# Sitara_Power.net
KiCad netlist of a schematic drawn in Altium Designer
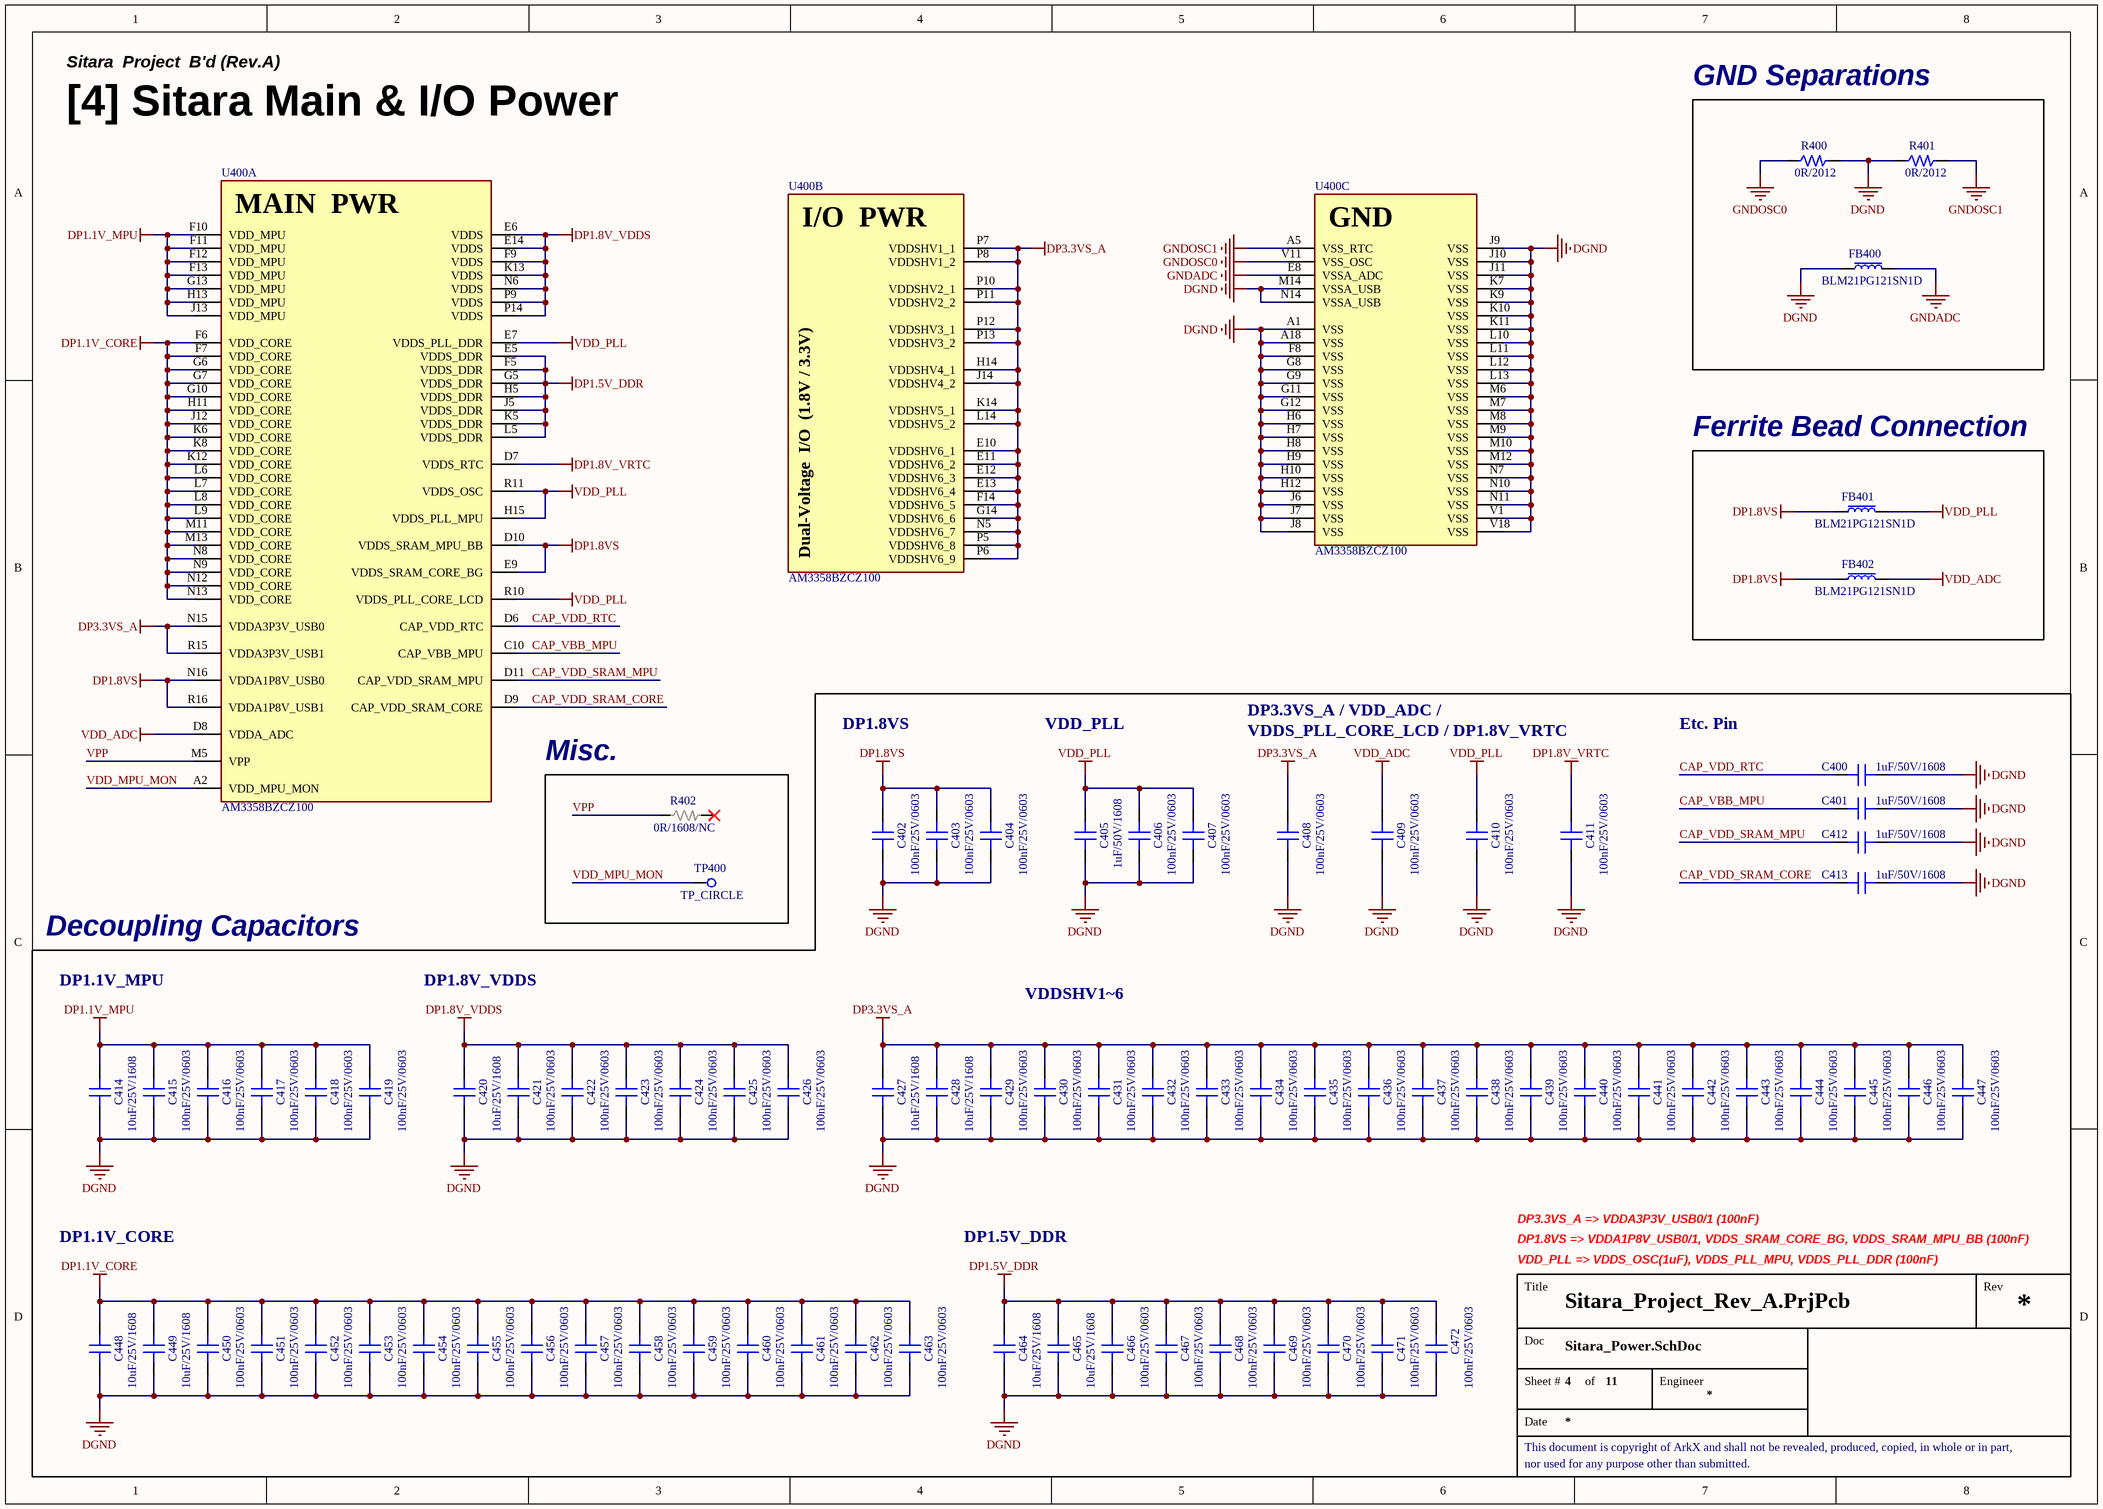
[diagram p0: Sitara_Power.SchDoc]

(export (version "E")
  (design (tool "Eeschema 10.0.6"))
  (components
    (comp (ref "C400")
      (value "1uF/50V/1608")
      (footprint "CAP 1608 (0603_INCH)")
      (description "Ceramic CAP_1uF/50V/1608")
      (fields (field (name "LCSC PART #") "C15849"))
      (libsource (lib "Arkx") (part "CAP_1uF/50V/1608"))
    )
    (comp (ref "C401")
      (value "1uF/50V/1608")
      (footprint "CAP 1608 (0603_INCH)")
      (description "Ceramic CAP_1uF/50V/1608")
      (fields (field (name "LCSC PART #") "C15849"))
      (libsource (lib "Arkx") (part "CAP_1uF/50V/1608"))
    )
    (comp (ref "C402")
      (value "100nF/25V/0603")
      (footprint "CAP 0603 (0201_INCH)")
      (description "Ceramic CAP_100nF/25V/0603")
      (fields (field (name "LCSC PART #") "C181047"))
      (libsource (lib "Arkx") (part "CAP_100nF/25V/0603"))
    )
    (comp (ref "C403")
      (value "100nF/25V/0603")
      (footprint "CAP 0603 (0201_INCH)")
      (description "Ceramic CAP_100nF/25V/0603")
      (fields (field (name "LCSC PART #") "C181047"))
      (libsource (lib "Arkx") (part "CAP_100nF/25V/0603"))
    )
    (comp (ref "C404")
      (value "100nF/25V/0603")
      (footprint "CAP 0603 (0201_INCH)")
      (description "Ceramic CAP_100nF/25V/0603")
      (fields (field (name "LCSC PART #") "C181047"))
      (libsource (lib "Arkx") (part "CAP_100nF/25V/0603"))
    )
    (comp (ref "C405")
      (value "1uF/50V/1608")
      (footprint "CAP 1608 (0603_INCH)")
      (description "Ceramic CAP_1uF/50V/1608")
      (fields (field (name "LCSC PART #") "C15849"))
      (libsource (lib "Arkx") (part "CAP_1uF/50V/1608"))
    )
    (comp (ref "C406")
      (value "100nF/25V/0603")
      (footprint "CAP 0603 (0201_INCH)")
      (description "Ceramic CAP_100nF/25V/0603")
      (fields (field (name "LCSC PART #") "C181047"))
      (libsource (lib "Arkx") (part "CAP_100nF/25V/0603"))
    )
    (comp (ref "C407")
      (value "100nF/25V/0603")
      (footprint "CAP 0603 (0201_INCH)")
      (description "Ceramic CAP_100nF/25V/0603")
      (fields (field (name "LCSC PART #") "C181047"))
      (libsource (lib "Arkx") (part "CAP_100nF/25V/0603"))
    )
    (comp (ref "C408")
      (value "100nF/25V/0603")
      (footprint "CAP 0603 (0201_INCH)")
      (description "Ceramic CAP_100nF/25V/0603")
      (fields (field (name "LCSC PART #") "C181047"))
      (libsource (lib "Arkx") (part "CAP_100nF/25V/0603"))
    )
    (comp (ref "C409")
      (value "100nF/25V/0603")
      (footprint "CAP 0603 (0201_INCH)")
      (description "Ceramic CAP_100nF/25V/0603")
      (fields (field (name "LCSC PART #") "C181047"))
      (libsource (lib "Arkx") (part "CAP_100nF/25V/0603"))
    )
    (comp (ref "C410")
      (value "100nF/25V/0603")
      (footprint "CAP 0603 (0201_INCH)")
      (description "Ceramic CAP_100nF/25V/0603")
      (fields (field (name "LCSC PART #") "C181047"))
      (libsource (lib "Arkx") (part "CAP_100nF/25V/0603"))
    )
    (comp (ref "C411")
      (value "100nF/25V/0603")
      (footprint "CAP 0603 (0201_INCH)")
      (description "Ceramic CAP_100nF/25V/0603")
      (fields (field (name "LCSC PART #") "C181047"))
      (libsource (lib "Arkx") (part "CAP_100nF/25V/0603"))
    )
    (comp (ref "C412")
      (value "1uF/50V/1608")
      (footprint "CAP 1608 (0603_INCH)")
      (description "Ceramic CAP_1uF/50V/1608")
      (fields (field (name "LCSC PART #") "C15849"))
      (libsource (lib "Arkx") (part "CAP_1uF/50V/1608"))
    )
    (comp (ref "C413")
      (value "1uF/50V/1608")
      (footprint "CAP 1608 (0603_INCH)")
      (description "Ceramic CAP_1uF/50V/1608")
      (fields (field (name "LCSC PART #") "C15849"))
      (libsource (lib "Arkx") (part "CAP_1uF/50V/1608"))
    )
    (comp (ref "C414")
      (value "10uF/25V/1608")
      (footprint "CAP 1608 (0603_INCH)")
      (description "Ceramic CAP_10uF/25V/1608")
      (fields (field (name "LCSC PART #") "C96446"))
      (libsource (lib "Arkx") (part "CAP_10uF/25V/1608"))
    )
    (comp (ref "C415")
      (value "100nF/25V/0603")
      (footprint "CAP 0603 (0201_INCH)")
      (description "Ceramic CAP_100nF/25V/0603")
      (fields (field (name "LCSC PART #") "C181047"))
      (libsource (lib "Arkx") (part "CAP_100nF/25V/0603"))
    )
    (comp (ref "C416")
      (value "100nF/25V/0603")
      (footprint "CAP 0603 (0201_INCH)")
      (description "Ceramic CAP_100nF/25V/0603")
      (fields (field (name "LCSC PART #") "C181047"))
      (libsource (lib "Arkx") (part "CAP_100nF/25V/0603"))
    )
    (comp (ref "C417")
      (value "100nF/25V/0603")
      (footprint "CAP 0603 (0201_INCH)")
      (description "Ceramic CAP_100nF/25V/0603")
      (fields (field (name "LCSC PART #") "C181047"))
      (libsource (lib "Arkx") (part "CAP_100nF/25V/0603"))
    )
    (comp (ref "C418")
      (value "100nF/25V/0603")
      (footprint "CAP 0603 (0201_INCH)")
      (description "Ceramic CAP_100nF/25V/0603")
      (fields (field (name "LCSC PART #") "C181047"))
      (libsource (lib "Arkx") (part "CAP_100nF/25V/0603"))
    )
    (comp (ref "C419")
      (value "100nF/25V/0603")
      (footprint "CAP 0603 (0201_INCH)")
      (description "Ceramic CAP_100nF/25V/0603")
      (fields (field (name "LCSC PART #") "C181047"))
      (libsource (lib "Arkx") (part "CAP_100nF/25V/0603"))
    )
    (comp (ref "C420")
      (value "10uF/25V/1608")
      (footprint "CAP 1608 (0603_INCH)")
      (description "Ceramic CAP_10uF/25V/1608")
      (fields (field (name "LCSC PART #") "C96446"))
      (libsource (lib "Arkx") (part "CAP_10uF/25V/1608"))
    )
    (comp (ref "C421")
      (value "100nF/25V/0603")
      (footprint "CAP 0603 (0201_INCH)")
      (description "Ceramic CAP_100nF/25V/0603")
      (fields (field (name "LCSC PART #") "C181047"))
      (libsource (lib "Arkx") (part "CAP_100nF/25V/0603"))
    )
    (comp (ref "C422")
      (value "100nF/25V/0603")
      (footprint "CAP 0603 (0201_INCH)")
      (description "Ceramic CAP_100nF/25V/0603")
      (fields (field (name "LCSC PART #") "C181047"))
      (libsource (lib "Arkx") (part "CAP_100nF/25V/0603"))
    )
    (comp (ref "C423")
      (value "100nF/25V/0603")
      (footprint "CAP 0603 (0201_INCH)")
      (description "Ceramic CAP_100nF/25V/0603")
      (fields (field (name "LCSC PART #") "C181047"))
      (libsource (lib "Arkx") (part "CAP_100nF/25V/0603"))
    )
    (comp (ref "C424")
      (value "100nF/25V/0603")
      (footprint "CAP 0603 (0201_INCH)")
      (description "Ceramic CAP_100nF/25V/0603")
      (fields (field (name "LCSC PART #") "C181047"))
      (libsource (lib "Arkx") (part "CAP_100nF/25V/0603"))
    )
    (comp (ref "C425")
      (value "100nF/25V/0603")
      (footprint "CAP 0603 (0201_INCH)")
      (description "Ceramic CAP_100nF/25V/0603")
      (fields (field (name "LCSC PART #") "C181047"))
      (libsource (lib "Arkx") (part "CAP_100nF/25V/0603"))
    )
    (comp (ref "C426")
      (value "100nF/25V/0603")
      (footprint "CAP 0603 (0201_INCH)")
      (description "Ceramic CAP_100nF/25V/0603")
      (fields (field (name "LCSC PART #") "C181047"))
      (libsource (lib "Arkx") (part "CAP_100nF/25V/0603"))
    )
    (comp (ref "C427")
      (value "10uF/25V/1608")
      (footprint "CAP 1608 (0603_INCH)")
      (description "Ceramic CAP_10uF/25V/1608")
      (fields (field (name "LCSC PART #") "C96446"))
      (libsource (lib "Arkx") (part "CAP_10uF/25V/1608"))
    )
    (comp (ref "C428")
      (value "10uF/25V/1608")
      (footprint "CAP 1608 (0603_INCH)")
      (description "Ceramic CAP_10uF/25V/1608")
      (fields (field (name "LCSC PART #") "C96446"))
      (libsource (lib "Arkx") (part "CAP_10uF/25V/1608"))
    )
    (comp (ref "C429")
      (value "100nF/25V/0603")
      (footprint "CAP 0603 (0201_INCH)")
      (description "Ceramic CAP_100nF/25V/0603")
      (fields (field (name "LCSC PART #") "C181047"))
      (libsource (lib "Arkx") (part "CAP_100nF/25V/0603"))
    )
    (comp (ref "C430")
      (value "100nF/25V/0603")
      (footprint "CAP 0603 (0201_INCH)")
      (description "Ceramic CAP_100nF/25V/0603")
      (fields (field (name "LCSC PART #") "C181047"))
      (libsource (lib "Arkx") (part "CAP_100nF/25V/0603"))
    )
    (comp (ref "C431")
      (value "100nF/25V/0603")
      (footprint "CAP 0603 (0201_INCH)")
      (description "Ceramic CAP_100nF/25V/0603")
      (fields (field (name "LCSC PART #") "C181047"))
      (libsource (lib "Arkx") (part "CAP_100nF/25V/0603"))
    )
    (comp (ref "C432")
      (value "100nF/25V/0603")
      (footprint "CAP 0603 (0201_INCH)")
      (description "Ceramic CAP_100nF/25V/0603")
      (fields (field (name "LCSC PART #") "C181047"))
      (libsource (lib "Arkx") (part "CAP_100nF/25V/0603"))
    )
    (comp (ref "C433")
      (value "100nF/25V/0603")
      (footprint "CAP 0603 (0201_INCH)")
      (description "Ceramic CAP_100nF/25V/0603")
      (fields (field (name "LCSC PART #") "C181047"))
      (libsource (lib "Arkx") (part "CAP_100nF/25V/0603"))
    )
    (comp (ref "C434")
      (value "100nF/25V/0603")
      (footprint "CAP 0603 (0201_INCH)")
      (description "Ceramic CAP_100nF/25V/0603")
      (fields (field (name "LCSC PART #") "C181047"))
      (libsource (lib "Arkx") (part "CAP_100nF/25V/0603"))
    )
    (comp (ref "C435")
      (value "100nF/25V/0603")
      (footprint "CAP 0603 (0201_INCH)")
      (description "Ceramic CAP_100nF/25V/0603")
      (fields (field (name "LCSC PART #") "C181047"))
      (libsource (lib "Arkx") (part "CAP_100nF/25V/0603"))
    )
    (comp (ref "C436")
      (value "100nF/25V/0603")
      (footprint "CAP 0603 (0201_INCH)")
      (description "Ceramic CAP_100nF/25V/0603")
      (fields (field (name "LCSC PART #") "C181047"))
      (libsource (lib "Arkx") (part "CAP_100nF/25V/0603"))
    )
    (comp (ref "C437")
      (value "100nF/25V/0603")
      (footprint "CAP 0603 (0201_INCH)")
      (description "Ceramic CAP_100nF/25V/0603")
      (fields (field (name "LCSC PART #") "C181047"))
      (libsource (lib "Arkx") (part "CAP_100nF/25V/0603"))
    )
    (comp (ref "C438")
      (value "100nF/25V/0603")
      (footprint "CAP 0603 (0201_INCH)")
      (description "Ceramic CAP_100nF/25V/0603")
      (fields (field (name "LCSC PART #") "C181047"))
      (libsource (lib "Arkx") (part "CAP_100nF/25V/0603"))
    )
    (comp (ref "C439")
      (value "100nF/25V/0603")
      (footprint "CAP 0603 (0201_INCH)")
      (description "Ceramic CAP_100nF/25V/0603")
      (fields (field (name "LCSC PART #") "C181047"))
      (libsource (lib "Arkx") (part "CAP_100nF/25V/0603"))
    )
    (comp (ref "C440")
      (value "100nF/25V/0603")
      (footprint "CAP 0603 (0201_INCH)")
      (description "Ceramic CAP_100nF/25V/0603")
      (fields (field (name "LCSC PART #") "C181047"))
      (libsource (lib "Arkx") (part "CAP_100nF/25V/0603"))
    )
    (comp (ref "C441")
      (value "100nF/25V/0603")
      (footprint "CAP 0603 (0201_INCH)")
      (description "Ceramic CAP_100nF/25V/0603")
      (fields (field (name "LCSC PART #") "C181047"))
      (libsource (lib "Arkx") (part "CAP_100nF/25V/0603"))
    )
    (comp (ref "C442")
      (value "100nF/25V/0603")
      (footprint "CAP 0603 (0201_INCH)")
      (description "Ceramic CAP_100nF/25V/0603")
      (fields (field (name "LCSC PART #") "C181047"))
      (libsource (lib "Arkx") (part "CAP_100nF/25V/0603"))
    )
    (comp (ref "C443")
      (value "100nF/25V/0603")
      (footprint "CAP 0603 (0201_INCH)")
      (description "Ceramic CAP_100nF/25V/0603")
      (fields (field (name "LCSC PART #") "C181047"))
      (libsource (lib "Arkx") (part "CAP_100nF/25V/0603"))
    )
    (comp (ref "C444")
      (value "100nF/25V/0603")
      (footprint "CAP 0603 (0201_INCH)")
      (description "Ceramic CAP_100nF/25V/0603")
      (fields (field (name "LCSC PART #") "C181047"))
      (libsource (lib "Arkx") (part "CAP_100nF/25V/0603"))
    )
    (comp (ref "C445")
      (value "100nF/25V/0603")
      (footprint "CAP 0603 (0201_INCH)")
      (description "Ceramic CAP_100nF/25V/0603")
      (fields (field (name "LCSC PART #") "C181047"))
      (libsource (lib "Arkx") (part "CAP_100nF/25V/0603"))
    )
    (comp (ref "C446")
      (value "100nF/25V/0603")
      (footprint "CAP 0603 (0201_INCH)")
      (description "Ceramic CAP_100nF/25V/0603")
      (fields (field (name "LCSC PART #") "C181047"))
      (libsource (lib "Arkx") (part "CAP_100nF/25V/0603"))
    )
    (comp (ref "C447")
      (value "100nF/25V/0603")
      (footprint "CAP 0603 (0201_INCH)")
      (description "Ceramic CAP_100nF/25V/0603")
      (fields (field (name "LCSC PART #") "C181047"))
      (libsource (lib "Arkx") (part "CAP_100nF/25V/0603"))
    )
    (comp (ref "C448")
      (value "10uF/25V/1608")
      (footprint "CAP 1608 (0603_INCH)")
      (description "Ceramic CAP_10uF/25V/1608")
      (fields (field (name "LCSC PART #") "C96446"))
      (libsource (lib "Arkx") (part "CAP_10uF/25V/1608"))
    )
    (comp (ref "C449")
      (value "10uF/25V/1608")
      (footprint "CAP 1608 (0603_INCH)")
      (description "Ceramic CAP_10uF/25V/1608")
      (fields (field (name "LCSC PART #") "C96446"))
      (libsource (lib "Arkx") (part "CAP_10uF/25V/1608"))
    )
    (comp (ref "C450")
      (value "100nF/25V/0603")
      (footprint "CAP 0603 (0201_INCH)")
      (description "Ceramic CAP_100nF/25V/0603")
      (fields (field (name "LCSC PART #") "C181047"))
      (libsource (lib "Arkx") (part "CAP_100nF/25V/0603"))
    )
    (comp (ref "C451")
      (value "100nF/25V/0603")
      (footprint "CAP 0603 (0201_INCH)")
      (description "Ceramic CAP_100nF/25V/0603")
      (fields (field (name "LCSC PART #") "C181047"))
      (libsource (lib "Arkx") (part "CAP_100nF/25V/0603"))
    )
    (comp (ref "C452")
      (value "100nF/25V/0603")
      (footprint "CAP 0603 (0201_INCH)")
      (description "Ceramic CAP_100nF/25V/0603")
      (fields (field (name "LCSC PART #") "C181047"))
      (libsource (lib "Arkx") (part "CAP_100nF/25V/0603"))
    )
    (comp (ref "C453")
      (value "100nF/25V/0603")
      (footprint "CAP 0603 (0201_INCH)")
      (description "Ceramic CAP_100nF/25V/0603")
      (fields (field (name "LCSC PART #") "C181047"))
      (libsource (lib "Arkx") (part "CAP_100nF/25V/0603"))
    )
    (comp (ref "C454")
      (value "100nF/25V/0603")
      (footprint "CAP 0603 (0201_INCH)")
      (description "Ceramic CAP_100nF/25V/0603")
      (fields (field (name "LCSC PART #") "C181047"))
      (libsource (lib "Arkx") (part "CAP_100nF/25V/0603"))
    )
    (comp (ref "C455")
      (value "100nF/25V/0603")
      (footprint "CAP 0603 (0201_INCH)")
      (description "Ceramic CAP_100nF/25V/0603")
      (fields (field (name "LCSC PART #") "C181047"))
      (libsource (lib "Arkx") (part "CAP_100nF/25V/0603"))
    )
    (comp (ref "C456")
      (value "100nF/25V/0603")
      (footprint "CAP 0603 (0201_INCH)")
      (description "Ceramic CAP_100nF/25V/0603")
      (fields (field (name "LCSC PART #") "C181047"))
      (libsource (lib "Arkx") (part "CAP_100nF/25V/0603"))
    )
    (comp (ref "C457")
      (value "100nF/25V/0603")
      (footprint "CAP 0603 (0201_INCH)")
      (description "Ceramic CAP_100nF/25V/0603")
      (fields (field (name "LCSC PART #") "C181047"))
      (libsource (lib "Arkx") (part "CAP_100nF/25V/0603"))
    )
    (comp (ref "C458")
      (value "100nF/25V/0603")
      (footprint "CAP 0603 (0201_INCH)")
      (description "Ceramic CAP_100nF/25V/0603")
      (fields (field (name "LCSC PART #") "C181047"))
      (libsource (lib "Arkx") (part "CAP_100nF/25V/0603"))
    )
    (comp (ref "C459")
      (value "100nF/25V/0603")
      (footprint "CAP 0603 (0201_INCH)")
      (description "Ceramic CAP_100nF/25V/0603")
      (fields (field (name "LCSC PART #") "C181047"))
      (libsource (lib "Arkx") (part "CAP_100nF/25V/0603"))
    )
    (comp (ref "C460")
      (value "100nF/25V/0603")
      (footprint "CAP 0603 (0201_INCH)")
      (description "Ceramic CAP_100nF/25V/0603")
      (fields (field (name "LCSC PART #") "C181047"))
      (libsource (lib "Arkx") (part "CAP_100nF/25V/0603"))
    )
    (comp (ref "C461")
      (value "100nF/25V/0603")
      (footprint "CAP 0603 (0201_INCH)")
      (description "Ceramic CAP_100nF/25V/0603")
      (fields (field (name "LCSC PART #") "C181047"))
      (libsource (lib "Arkx") (part "CAP_100nF/25V/0603"))
    )
    (comp (ref "C462")
      (value "100nF/25V/0603")
      (footprint "CAP 0603 (0201_INCH)")
      (description "Ceramic CAP_100nF/25V/0603")
      (fields (field (name "LCSC PART #") "C181047"))
      (libsource (lib "Arkx") (part "CAP_100nF/25V/0603"))
    )
    (comp (ref "C463")
      (value "100nF/25V/0603")
      (footprint "CAP 0603 (0201_INCH)")
      (description "Ceramic CAP_100nF/25V/0603")
      (fields (field (name "LCSC PART #") "C181047"))
      (libsource (lib "Arkx") (part "CAP_100nF/25V/0603"))
    )
    (comp (ref "C464")
      (value "10uF/25V/1608")
      (footprint "CAP 1608 (0603_INCH)")
      (description "Ceramic CAP_10uF/25V/1608")
      (fields (field (name "LCSC PART #") "C96446"))
      (libsource (lib "Arkx") (part "CAP_10uF/25V/1608"))
    )
    (comp (ref "C465")
      (value "10uF/25V/1608")
      (footprint "CAP 1608 (0603_INCH)")
      (description "Ceramic CAP_10uF/25V/1608")
      (fields (field (name "LCSC PART #") "C96446"))
      (libsource (lib "Arkx") (part "CAP_10uF/25V/1608"))
    )
    (comp (ref "C466")
      (value "100nF/25V/0603")
      (footprint "CAP 0603 (0201_INCH)")
      (description "Ceramic CAP_100nF/25V/0603")
      (fields (field (name "LCSC PART #") "C181047"))
      (libsource (lib "Arkx") (part "CAP_100nF/25V/0603"))
    )
    (comp (ref "C467")
      (value "100nF/25V/0603")
      (footprint "CAP 0603 (0201_INCH)")
      (description "Ceramic CAP_100nF/25V/0603")
      (fields (field (name "LCSC PART #") "C181047"))
      (libsource (lib "Arkx") (part "CAP_100nF/25V/0603"))
    )
    (comp (ref "C468")
      (value "100nF/25V/0603")
      (footprint "CAP 0603 (0201_INCH)")
      (description "Ceramic CAP_100nF/25V/0603")
      (fields (field (name "LCSC PART #") "C181047"))
      (libsource (lib "Arkx") (part "CAP_100nF/25V/0603"))
    )
    (comp (ref "C469")
      (value "100nF/25V/0603")
      (footprint "CAP 0603 (0201_INCH)")
      (description "Ceramic CAP_100nF/25V/0603")
      (fields (field (name "LCSC PART #") "C181047"))
      (libsource (lib "Arkx") (part "CAP_100nF/25V/0603"))
    )
    (comp (ref "C470")
      (value "100nF/25V/0603")
      (footprint "CAP 0603 (0201_INCH)")
      (description "Ceramic CAP_100nF/25V/0603")
      (fields (field (name "LCSC PART #") "C181047"))
      (libsource (lib "Arkx") (part "CAP_100nF/25V/0603"))
    )
    (comp (ref "C471")
      (value "100nF/25V/0603")
      (footprint "CAP 0603 (0201_INCH)")
      (description "Ceramic CAP_100nF/25V/0603")
      (fields (field (name "LCSC PART #") "C181047"))
      (libsource (lib "Arkx") (part "CAP_100nF/25V/0603"))
    )
    (comp (ref "C472")
      (value "100nF/25V/0603")
      (footprint "CAP 0603 (0201_INCH)")
      (description "Ceramic CAP_100nF/25V/0603")
      (fields (field (name "LCSC PART #") "C181047"))
      (libsource (lib "Arkx") (part "CAP_100nF/25V/0603"))
    )
    (comp (ref "FB400")
      (value "BLM21PG121SN1D")
      (footprint "FB 2012 (0805_inch)")
      (description "3A 1 30mΩ 120Ω@100MHz ±25% 0805  Ferrite Beads ROHS")
      (fields (field (name "LCSC PART #") "C79382"))
      (libsource (lib "Arkx") (part "FB_BLM21PG121SN1D"))
    )
    (comp (ref "FB401")
      (value "BLM21PG121SN1D")
      (footprint "FB 2012 (0805_inch)")
      (description "3A 1 30mΩ 120Ω@100MHz ±25% 0805  Ferrite Beads ROHS")
      (fields (field (name "LCSC PART #") "C79382"))
      (libsource (lib "Arkx") (part "FB_BLM21PG121SN1D"))
    )
    (comp (ref "FB402")
      (value "BLM21PG121SN1D")
      (footprint "FB 2012 (0805_inch)")
      (description "3A 1 30mΩ 120Ω@100MHz ±25% 0805  Ferrite Beads ROHS")
      (fields (field (name "LCSC PART #") "C79382"))
      (libsource (lib "Arkx") (part "FB_BLM21PG121SN1D"))
    )
    (comp (ref "R400")
      (value "0R/2012")
      (footprint "RES 2012 (0805_inch)")
      (description "RES_0R/2012/0.125W")
      (fields (field (name "LCSC PART #") "C17477"))
      (libsource (lib "Arkx") (part "RES_0R/2012/0.125W"))
    )
    (comp (ref "R401")
      (value "0R/2012")
      (footprint "RES 2012 (0805_inch)")
      (description "RES_0R/2012/0.125W")
      (fields (field (name "LCSC PART #") "C17477"))
      (libsource (lib "Arkx") (part "RES_0R/2012/0.125W"))
    )
    (comp (ref "R402")
      (value "0R/1608/NC")
      (footprint "RES 1608 (0603_inch)/NC")
      (description "0R/1608/0.1W/NC")
      (libsource (lib "Arkx") (part "RES_NC_0R/1608/0.1W"))
    )
    (comp (ref "TP400")
      (value "TP_CIRCLE")
      (footprint "TP Circle")
      (libsource (lib "Arkx") (part "TP_CIRCLE"))
    )
    (comp (ref "U400")
      (value "AM3358BZCZ100")
      (footprint "IC_SOC_AM3358BZCZ100")
      (description "ARM® Cortex®-A8 Microprocessor IC Sitara™ 1 Core, 32-Bit 1.0GHz 324-NFBGA (15x15)")
      (fields (field (name "LCSC PART #") "C73932"))
      (libsource (lib "Arkx") (part "IC_SOC_AM3358BZCZ100"))
    )
  )
  (nets
    (net (code "1") (name "/CAP_VBB_MPU") (class "Default")
      (node (ref "C401") (pin "1") (pinfunction "1_1") (pintype "passive"))
      (node (ref "U400") (pin "C10") (pinfunction "CAP_VBB_MPU_C10") (pintype "power_in"))
    )
    (net (code "2") (name "/CAP_VDD_RTC") (class "Default")
      (node (ref "C400") (pin "1") (pinfunction "1_1") (pintype "passive"))
      (node (ref "U400") (pin "D6") (pinfunction "CAP_VDD_RTC_D6") (pintype "power_in"))
    )
    (net (code "3") (name "/CAP_VDD_SRAM_CORE") (class "Default")
      (node (ref "C413") (pin "1") (pinfunction "1_1") (pintype "passive"))
      (node (ref "U400") (pin "D9") (pinfunction "CAP_VDD_SRAM_CORE_D9") (pintype "power_in"))
    )
    (net (code "4") (name "/CAP_VDD_SRAM_MPU") (class "Default")
      (node (ref "C412") (pin "1") (pinfunction "1_1") (pintype "passive"))
      (node (ref "U400") (pin "D11") (pinfunction "CAP_VDD_SRAM_MPU_D11") (pintype "power_in"))
    )
    (net (code "5") (name "/VDD_MPU_MON") (class "Default")
      (node (ref "TP400") (pin "1") (pinfunction "TP_1") (pintype "passive"))
      (node (ref "U400") (pin "A2") (pinfunction "VDD_MPU_MON_A2") (pintype "power_in"))
    )
    (net (code "6") (name "/VPP") (class "Default")
      (node (ref "R402") (pin "1") (pinfunction "1_1") (pintype "passive"))
      (node (ref "U400") (pin "M5") (pinfunction "VPP_M5") (pintype "power_in"))
    )
    (net (code "7") (name "DGND") (class "Default")
      (node (ref "C400") (pin "2") (pinfunction "2_2") (pintype "passive"))
      (node (ref "C401") (pin "2") (pinfunction "2_2") (pintype "passive"))
      (node (ref "C402") (pin "1") (pinfunction "1_1") (pintype "passive"))
      (node (ref "C403") (pin "1") (pinfunction "1_1") (pintype "passive"))
      (node (ref "C404") (pin "1") (pinfunction "1_1") (pintype "passive"))
      (node (ref "C405") (pin "1") (pinfunction "1_1") (pintype "passive"))
      (node (ref "C406") (pin "1") (pinfunction "1_1") (pintype "passive"))
      (node (ref "C407") (pin "1") (pinfunction "1_1") (pintype "passive"))
      (node (ref "C408") (pin "1") (pinfunction "1_1") (pintype "passive"))
      (node (ref "C409") (pin "1") (pinfunction "1_1") (pintype "passive"))
      (node (ref "C410") (pin "1") (pinfunction "1_1") (pintype "passive"))
      (node (ref "C411") (pin "1") (pinfunction "1_1") (pintype "passive"))
      (node (ref "C412") (pin "2") (pinfunction "2_2") (pintype "passive"))
      (node (ref "C413") (pin "2") (pinfunction "2_2") (pintype "passive"))
      (node (ref "C414") (pin "1") (pinfunction "1_1") (pintype "passive"))
      (node (ref "C415") (pin "1") (pinfunction "1_1") (pintype "passive"))
      (node (ref "C416") (pin "1") (pinfunction "1_1") (pintype "passive"))
      (node (ref "C417") (pin "1") (pinfunction "1_1") (pintype "passive"))
      (node (ref "C418") (pin "1") (pinfunction "1_1") (pintype "passive"))
      (node (ref "C419") (pin "1") (pinfunction "1_1") (pintype "passive"))
      (node (ref "C420") (pin "1") (pinfunction "1_1") (pintype "passive"))
      (node (ref "C421") (pin "1") (pinfunction "1_1") (pintype "passive"))
      (node (ref "C422") (pin "1") (pinfunction "1_1") (pintype "passive"))
      (node (ref "C423") (pin "1") (pinfunction "1_1") (pintype "passive"))
      (node (ref "C424") (pin "1") (pinfunction "1_1") (pintype "passive"))
      (node (ref "C425") (pin "1") (pinfunction "1_1") (pintype "passive"))
      (node (ref "C426") (pin "1") (pinfunction "1_1") (pintype "passive"))
      (node (ref "C427") (pin "1") (pinfunction "1_1") (pintype "passive"))
      (node (ref "C428") (pin "1") (pinfunction "1_1") (pintype "passive"))
      (node (ref "C429") (pin "1") (pinfunction "1_1") (pintype "passive"))
      (node (ref "C430") (pin "1") (pinfunction "1_1") (pintype "passive"))
      (node (ref "C431") (pin "1") (pinfunction "1_1") (pintype "passive"))
      (node (ref "C432") (pin "1") (pinfunction "1_1") (pintype "passive"))
      (node (ref "C433") (pin "1") (pinfunction "1_1") (pintype "passive"))
      (node (ref "C434") (pin "1") (pinfunction "1_1") (pintype "passive"))
      (node (ref "C435") (pin "1") (pinfunction "1_1") (pintype "passive"))
      (node (ref "C436") (pin "1") (pinfunction "1_1") (pintype "passive"))
      (node (ref "C437") (pin "1") (pinfunction "1_1") (pintype "passive"))
      (node (ref "C438") (pin "1") (pinfunction "1_1") (pintype "passive"))
      (node (ref "C439") (pin "1") (pinfunction "1_1") (pintype "passive"))
      (node (ref "C440") (pin "1") (pinfunction "1_1") (pintype "passive"))
      (node (ref "C441") (pin "1") (pinfunction "1_1") (pintype "passive"))
      (node (ref "C442") (pin "1") (pinfunction "1_1") (pintype "passive"))
      (node (ref "C443") (pin "1") (pinfunction "1_1") (pintype "passive"))
      (node (ref "C444") (pin "1") (pinfunction "1_1") (pintype "passive"))
      (node (ref "C445") (pin "1") (pinfunction "1_1") (pintype "passive"))
      (node (ref "C446") (pin "1") (pinfunction "1_1") (pintype "passive"))
      (node (ref "C447") (pin "1") (pinfunction "1_1") (pintype "passive"))
      (node (ref "C448") (pin "1") (pinfunction "1_1") (pintype "passive"))
      (node (ref "C449") (pin "1") (pinfunction "1_1") (pintype "passive"))
      (node (ref "C450") (pin "1") (pinfunction "1_1") (pintype "passive"))
      (node (ref "C451") (pin "1") (pinfunction "1_1") (pintype "passive"))
      (node (ref "C452") (pin "1") (pinfunction "1_1") (pintype "passive"))
      (node (ref "C453") (pin "1") (pinfunction "1_1") (pintype "passive"))
      (node (ref "C454") (pin "1") (pinfunction "1_1") (pintype "passive"))
      (node (ref "C455") (pin "1") (pinfunction "1_1") (pintype "passive"))
      (node (ref "C456") (pin "1") (pinfunction "1_1") (pintype "passive"))
      (node (ref "C457") (pin "1") (pinfunction "1_1") (pintype "passive"))
      (node (ref "C458") (pin "1") (pinfunction "1_1") (pintype "passive"))
      (node (ref "C459") (pin "1") (pinfunction "1_1") (pintype "passive"))
      (node (ref "C460") (pin "1") (pinfunction "1_1") (pintype "passive"))
      (node (ref "C461") (pin "1") (pinfunction "1_1") (pintype "passive"))
      (node (ref "C462") (pin "1") (pinfunction "1_1") (pintype "passive"))
      (node (ref "C463") (pin "1") (pinfunction "1_1") (pintype "passive"))
      (node (ref "C464") (pin "1") (pinfunction "1_1") (pintype "passive"))
      (node (ref "C465") (pin "1") (pinfunction "1_1") (pintype "passive"))
      (node (ref "C466") (pin "1") (pinfunction "1_1") (pintype "passive"))
      (node (ref "C467") (pin "1") (pinfunction "1_1") (pintype "passive"))
      (node (ref "C468") (pin "1") (pinfunction "1_1") (pintype "passive"))
      (node (ref "C469") (pin "1") (pinfunction "1_1") (pintype "passive"))
      (node (ref "C470") (pin "1") (pinfunction "1_1") (pintype "passive"))
      (node (ref "C471") (pin "1") (pinfunction "1_1") (pintype "passive"))
      (node (ref "C472") (pin "1") (pinfunction "1_1") (pintype "passive"))
      (node (ref "FB400") (pin "1") (pinfunction "1_1") (pintype "passive"))
      (node (ref "R400") (pin "2") (pinfunction "2_2") (pintype "passive"))
      (node (ref "R401") (pin "1") (pinfunction "1_1") (pintype "passive"))
      (node (ref "U400") (pin "A1") (pinfunction "VSS_A1") (pintype "power_in"))
      (node (ref "U400") (pin "A18") (pinfunction "VSS_A18") (pintype "power_in"))
      (node (ref "U400") (pin "F8") (pinfunction "VSS_F8") (pintype "power_in"))
      (node (ref "U400") (pin "G11") (pinfunction "VSS_G11") (pintype "power_in"))
      (node (ref "U400") (pin "G12") (pinfunction "VSS_G12") (pintype "power_in"))
      (node (ref "U400") (pin "G8") (pinfunction "VSS_G8") (pintype "power_in"))
      (node (ref "U400") (pin "G9") (pinfunction "VSS_G9") (pintype "power_in"))
      (node (ref "U400") (pin "H10") (pinfunction "VSS_H10") (pintype "power_in"))
      (node (ref "U400") (pin "H12") (pinfunction "VSS_H12") (pintype "power_in"))
      (node (ref "U400") (pin "H6") (pinfunction "VSS_H6") (pintype "power_in"))
      (node (ref "U400") (pin "H7") (pinfunction "VSS_H7") (pintype "power_in"))
      (node (ref "U400") (pin "H8") (pinfunction "VSS_H8") (pintype "power_in"))
      (node (ref "U400") (pin "H9") (pinfunction "VSS_H9") (pintype "power_in"))
      (node (ref "U400") (pin "J10") (pinfunction "VSS_J10") (pintype "power_in"))
      (node (ref "U400") (pin "J11") (pinfunction "VSS_J11") (pintype "power_in"))
      (node (ref "U400") (pin "J6") (pinfunction "VSS_J6") (pintype "power_in"))
      (node (ref "U400") (pin "J7") (pinfunction "VSS_J7") (pintype "power_in"))
      (node (ref "U400") (pin "J8") (pinfunction "VSS_J8") (pintype "power_in"))
      (node (ref "U400") (pin "J9") (pinfunction "VSS_J9") (pintype "power_in"))
      (node (ref "U400") (pin "K10") (pinfunction "VSS_K10") (pintype "power_in"))
      (node (ref "U400") (pin "K11") (pinfunction "VSS_K11") (pintype "power_in"))
      (node (ref "U400") (pin "K7") (pinfunction "VSS_K7") (pintype "power_in"))
      (node (ref "U400") (pin "K9") (pinfunction "VSS_K9") (pintype "power_in"))
      (node (ref "U400") (pin "L10") (pinfunction "VSS_L10") (pintype "power_in"))
      (node (ref "U400") (pin "L11") (pinfunction "VSS_L11") (pintype "power_in"))
      (node (ref "U400") (pin "L12") (pinfunction "VSS_L12") (pintype "power_in"))
      (node (ref "U400") (pin "L13") (pinfunction "VSS_L13") (pintype "power_in"))
      (node (ref "U400") (pin "M10") (pinfunction "VSS_M10") (pintype "power_in"))
      (node (ref "U400") (pin "M12") (pinfunction "VSS_M12") (pintype "power_in"))
      (node (ref "U400") (pin "M14") (pinfunction "VSSA_USB_M14") (pintype "power_in"))
      (node (ref "U400") (pin "M6") (pinfunction "VSS_M6") (pintype "power_in"))
      (node (ref "U400") (pin "M7") (pinfunction "VSS_M7") (pintype "power_in"))
      (node (ref "U400") (pin "M8") (pinfunction "VSS_M8") (pintype "power_in"))
      (node (ref "U400") (pin "M9") (pinfunction "VSS_M9") (pintype "power_in"))
      (node (ref "U400") (pin "N10") (pinfunction "VSS_N10") (pintype "power_in"))
      (node (ref "U400") (pin "N11") (pinfunction "VSS_N11") (pintype "power_in"))
      (node (ref "U400") (pin "N14") (pinfunction "VSSA_USB_N14") (pintype "power_in"))
      (node (ref "U400") (pin "N7") (pinfunction "VSS_N7") (pintype "power_in"))
      (node (ref "U400") (pin "V1") (pinfunction "VSS_V1") (pintype "power_in"))
      (node (ref "U400") (pin "V18") (pinfunction "VSS_V18") (pintype "power_in"))
    )
    (net (code "8") (name "DP1.1V_CORE") (class "Default")
      (node (ref "C448") (pin "2") (pinfunction "2_2") (pintype "passive"))
      (node (ref "C449") (pin "2") (pinfunction "2_2") (pintype "passive"))
      (node (ref "C450") (pin "2") (pinfunction "2_2") (pintype "passive"))
      (node (ref "C451") (pin "2") (pinfunction "2_2") (pintype "passive"))
      (node (ref "C452") (pin "2") (pinfunction "2_2") (pintype "passive"))
      (node (ref "C453") (pin "2") (pinfunction "2_2") (pintype "passive"))
      (node (ref "C454") (pin "2") (pinfunction "2_2") (pintype "passive"))
      (node (ref "C455") (pin "2") (pinfunction "2_2") (pintype "passive"))
      (node (ref "C456") (pin "2") (pinfunction "2_2") (pintype "passive"))
      (node (ref "C457") (pin "2") (pinfunction "2_2") (pintype "passive"))
      (node (ref "C458") (pin "2") (pinfunction "2_2") (pintype "passive"))
      (node (ref "C459") (pin "2") (pinfunction "2_2") (pintype "passive"))
      (node (ref "C460") (pin "2") (pinfunction "2_2") (pintype "passive"))
      (node (ref "C461") (pin "2") (pinfunction "2_2") (pintype "passive"))
      (node (ref "C462") (pin "2") (pinfunction "2_2") (pintype "passive"))
      (node (ref "C463") (pin "2") (pinfunction "2_2") (pintype "passive"))
      (node (ref "U400") (pin "F6") (pinfunction "VDD_CORE_F6") (pintype "power_in"))
      (node (ref "U400") (pin "F7") (pinfunction "VDD_CORE_F7") (pintype "power_in"))
      (node (ref "U400") (pin "G10") (pinfunction "VDD_CORE_G10") (pintype "power_in"))
      (node (ref "U400") (pin "G6") (pinfunction "VDD_CORE_G6") (pintype "power_in"))
      (node (ref "U400") (pin "G7") (pinfunction "VDD_CORE_G7") (pintype "power_in"))
      (node (ref "U400") (pin "H11") (pinfunction "VDD_CORE_H11") (pintype "power_in"))
      (node (ref "U400") (pin "J12") (pinfunction "VDD_CORE_J12") (pintype "power_in"))
      (node (ref "U400") (pin "K12") (pinfunction "VDD_CORE_K12") (pintype "power_in"))
      (node (ref "U400") (pin "K6") (pinfunction "VDD_CORE_K6") (pintype "power_in"))
      (node (ref "U400") (pin "K8") (pinfunction "VDD_CORE_K8") (pintype "power_in"))
      (node (ref "U400") (pin "L6") (pinfunction "VDD_CORE_L6") (pintype "power_in"))
      (node (ref "U400") (pin "L7") (pinfunction "VDD_CORE_L7") (pintype "power_in"))
      (node (ref "U400") (pin "L8") (pinfunction "VDD_CORE_L8") (pintype "power_in"))
      (node (ref "U400") (pin "L9") (pinfunction "VDD_CORE_L9") (pintype "power_in"))
      (node (ref "U400") (pin "M11") (pinfunction "VDD_CORE_M11") (pintype "power_in"))
      (node (ref "U400") (pin "M13") (pinfunction "VDD_CORE_M13") (pintype "power_in"))
      (node (ref "U400") (pin "N12") (pinfunction "VDD_CORE_N12") (pintype "power_in"))
      (node (ref "U400") (pin "N13") (pinfunction "VDD_CORE_N13") (pintype "power_in"))
      (node (ref "U400") (pin "N8") (pinfunction "VDD_CORE_N8") (pintype "power_in"))
      (node (ref "U400") (pin "N9") (pinfunction "VDD_CORE_N9") (pintype "power_in"))
    )
    (net (code "9") (name "DP1.1V_MPU") (class "Default")
      (node (ref "C414") (pin "2") (pinfunction "2_2") (pintype "passive"))
      (node (ref "C415") (pin "2") (pinfunction "2_2") (pintype "passive"))
      (node (ref "C416") (pin "2") (pinfunction "2_2") (pintype "passive"))
      (node (ref "C417") (pin "2") (pinfunction "2_2") (pintype "passive"))
      (node (ref "C418") (pin "2") (pinfunction "2_2") (pintype "passive"))
      (node (ref "C419") (pin "2") (pinfunction "2_2") (pintype "passive"))
      (node (ref "U400") (pin "F10") (pinfunction "VDD_MPU_F10") (pintype "power_in"))
      (node (ref "U400") (pin "F11") (pinfunction "VDD_MPU_F11") (pintype "power_in"))
      (node (ref "U400") (pin "F12") (pinfunction "VDD_MPU_F12") (pintype "power_in"))
      (node (ref "U400") (pin "F13") (pinfunction "VDD_MPU_F13") (pintype "power_in"))
      (node (ref "U400") (pin "G13") (pinfunction "VDD_MPU_G13") (pintype "power_in"))
      (node (ref "U400") (pin "H13") (pinfunction "VDD_MPU_H13") (pintype "power_in"))
      (node (ref "U400") (pin "J13") (pinfunction "VDD_MPU_J13") (pintype "power_in"))
    )
    (net (code "10") (name "DP1.5V_DDR") (class "Default")
      (node (ref "C464") (pin "2") (pinfunction "2_2") (pintype "passive"))
      (node (ref "C465") (pin "2") (pinfunction "2_2") (pintype "passive"))
      (node (ref "C466") (pin "2") (pinfunction "2_2") (pintype "passive"))
      (node (ref "C467") (pin "2") (pinfunction "2_2") (pintype "passive"))
      (node (ref "C468") (pin "2") (pinfunction "2_2") (pintype "passive"))
      (node (ref "C469") (pin "2") (pinfunction "2_2") (pintype "passive"))
      (node (ref "C470") (pin "2") (pinfunction "2_2") (pintype "passive"))
      (node (ref "C471") (pin "2") (pinfunction "2_2") (pintype "passive"))
      (node (ref "C472") (pin "2") (pinfunction "2_2") (pintype "passive"))
      (node (ref "U400") (pin "E5") (pinfunction "VDDS_DDR_E5") (pintype "power_in"))
      (node (ref "U400") (pin "F5") (pinfunction "VDDS_DDR_F5") (pintype "power_in"))
      (node (ref "U400") (pin "G5") (pinfunction "VDDS_DDR_G5") (pintype "power_in"))
      (node (ref "U400") (pin "H5") (pinfunction "VDDS_DDR_H5") (pintype "power_in"))
      (node (ref "U400") (pin "J5") (pinfunction "VDDS_DDR_J5") (pintype "power_in"))
      (node (ref "U400") (pin "K5") (pinfunction "VDDS_DDR_K5") (pintype "power_in"))
      (node (ref "U400") (pin "L5") (pinfunction "VDDS_DDR_L5") (pintype "power_in"))
    )
    (net (code "11") (name "DP1.8VS") (class "Default")
      (node (ref "C402") (pin "2") (pinfunction "2_2") (pintype "passive"))
      (node (ref "C403") (pin "2") (pinfunction "2_2") (pintype "passive"))
      (node (ref "C404") (pin "2") (pinfunction "2_2") (pintype "passive"))
      (node (ref "FB401") (pin "1") (pinfunction "1_1") (pintype "passive"))
      (node (ref "FB402") (pin "1") (pinfunction "1_1") (pintype "passive"))
      (node (ref "U400") (pin "D10") (pinfunction "VDDS_SRAM_MPU_BB_D10") (pintype "power_in"))
      (node (ref "U400") (pin "E9") (pinfunction "VDDS_SRAM_CORE_BG_E9") (pintype "power_in"))
      (node (ref "U400") (pin "N16") (pinfunction "VDDA1P8V_USB0_N16") (pintype "power_in"))
      (node (ref "U400") (pin "R16") (pinfunction "VDDA1P8V_USB1_R16") (pintype "power_in"))
    )
    (net (code "12") (name "DP1.8V_VDDS") (class "Default")
      (node (ref "C420") (pin "2") (pinfunction "2_2") (pintype "passive"))
      (node (ref "C421") (pin "2") (pinfunction "2_2") (pintype "passive"))
      (node (ref "C422") (pin "2") (pinfunction "2_2") (pintype "passive"))
      (node (ref "C423") (pin "2") (pinfunction "2_2") (pintype "passive"))
      (node (ref "C424") (pin "2") (pinfunction "2_2") (pintype "passive"))
      (node (ref "C425") (pin "2") (pinfunction "2_2") (pintype "passive"))
      (node (ref "C426") (pin "2") (pinfunction "2_2") (pintype "passive"))
      (node (ref "U400") (pin "E14") (pinfunction "VDDS_E14") (pintype "power_in"))
      (node (ref "U400") (pin "E6") (pinfunction "VDDS_E6") (pintype "power_in"))
      (node (ref "U400") (pin "F9") (pinfunction "VDDS_F9") (pintype "power_in"))
      (node (ref "U400") (pin "K13") (pinfunction "VDDS_K13") (pintype "power_in"))
      (node (ref "U400") (pin "N6") (pinfunction "VDDS_N6") (pintype "power_in"))
      (node (ref "U400") (pin "P14") (pinfunction "VDDS_P14") (pintype "power_in"))
      (node (ref "U400") (pin "P9") (pinfunction "VDDS_P9") (pintype "power_in"))
    )
    (net (code "13") (name "DP1.8V_VRTC") (class "Default")
      (node (ref "C411") (pin "2") (pinfunction "2_2") (pintype "passive"))
      (node (ref "U400") (pin "D7") (pinfunction "VDDS_RTC_D7") (pintype "power_in"))
    )
    (net (code "14") (name "DP3.3VS_A") (class "Default")
      (node (ref "C408") (pin "2") (pinfunction "2_2") (pintype "passive"))
      (node (ref "C427") (pin "2") (pinfunction "2_2") (pintype "passive"))
      (node (ref "C428") (pin "2") (pinfunction "2_2") (pintype "passive"))
      (node (ref "C429") (pin "2") (pinfunction "2_2") (pintype "passive"))
      (node (ref "C430") (pin "2") (pinfunction "2_2") (pintype "passive"))
      (node (ref "C431") (pin "2") (pinfunction "2_2") (pintype "passive"))
      (node (ref "C432") (pin "2") (pinfunction "2_2") (pintype "passive"))
      (node (ref "C433") (pin "2") (pinfunction "2_2") (pintype "passive"))
      (node (ref "C434") (pin "2") (pinfunction "2_2") (pintype "passive"))
      (node (ref "C435") (pin "2") (pinfunction "2_2") (pintype "passive"))
      (node (ref "C436") (pin "2") (pinfunction "2_2") (pintype "passive"))
      (node (ref "C437") (pin "2") (pinfunction "2_2") (pintype "passive"))
      (node (ref "C438") (pin "2") (pinfunction "2_2") (pintype "passive"))
      (node (ref "C439") (pin "2") (pinfunction "2_2") (pintype "passive"))
      (node (ref "C440") (pin "2") (pinfunction "2_2") (pintype "passive"))
      (node (ref "C441") (pin "2") (pinfunction "2_2") (pintype "passive"))
      (node (ref "C442") (pin "2") (pinfunction "2_2") (pintype "passive"))
      (node (ref "C443") (pin "2") (pinfunction "2_2") (pintype "passive"))
      (node (ref "C444") (pin "2") (pinfunction "2_2") (pintype "passive"))
      (node (ref "C445") (pin "2") (pinfunction "2_2") (pintype "passive"))
      (node (ref "C446") (pin "2") (pinfunction "2_2") (pintype "passive"))
      (node (ref "C447") (pin "2") (pinfunction "2_2") (pintype "passive"))
      (node (ref "U400") (pin "E10") (pinfunction "VDDSHV6_1_E10") (pintype "power_in"))
      (node (ref "U400") (pin "E11") (pinfunction "VDDSHV6_2_E11") (pintype "power_in"))
      (node (ref "U400") (pin "E12") (pinfunction "VDDSHV6_3_E12") (pintype "power_in"))
      (node (ref "U400") (pin "E13") (pinfunction "VDDSHV6_4_E13") (pintype "power_in"))
      (node (ref "U400") (pin "F14") (pinfunction "VDDSHV6_5_F14") (pintype "power_in"))
      (node (ref "U400") (pin "G14") (pinfunction "VDDSHV6_6_G14") (pintype "power_in"))
      (node (ref "U400") (pin "H14") (pinfunction "VDDSHV4_1_H14") (pintype "power_in"))
      (node (ref "U400") (pin "J14") (pinfunction "VDDSHV4_2_J14") (pintype "power_in"))
      (node (ref "U400") (pin "K14") (pinfunction "VDDSHV5_1_K14") (pintype "power_in"))
      (node (ref "U400") (pin "L14") (pinfunction "VDDSHV5_2_L14") (pintype "power_in"))
      (node (ref "U400") (pin "N15") (pinfunction "VDDA3P3V_USB0_N15") (pintype "power_in"))
      (node (ref "U400") (pin "N5") (pinfunction "VDDSHV6_7_N5") (pintype "power_in"))
      (node (ref "U400") (pin "P10") (pinfunction "VDDSHV2_1_P10") (pintype "power_in"))
      (node (ref "U400") (pin "P11") (pinfunction "VDDSHV2_2_P11") (pintype "power_in"))
      (node (ref "U400") (pin "P12") (pinfunction "VDDSHV3_1_P12") (pintype "power_in"))
      (node (ref "U400") (pin "P13") (pinfunction "VDDSHV3_2_P13") (pintype "power_in"))
      (node (ref "U400") (pin "P5") (pinfunction "VDDSHV6_8_P5") (pintype "power_in"))
      (node (ref "U400") (pin "P6") (pinfunction "VDDSHV6_9_P6") (pintype "power_in"))
      (node (ref "U400") (pin "P7") (pinfunction "VDDSHV1_1_P7") (pintype "power_in"))
      (node (ref "U400") (pin "P8") (pinfunction "VDDSHV1_2_P8") (pintype "power_in"))
      (node (ref "U400") (pin "R15") (pinfunction "VDDA3P3V_USB1_R15") (pintype "power_in"))
    )
    (net (code "15") (name "GNDADC") (class "Default")
      (node (ref "FB400") (pin "2") (pinfunction "2_2") (pintype "passive"))
      (node (ref "U400") (pin "E8") (pinfunction "VSSA_ADC_E8") (pintype "power_in"))
    )
    (net (code "16") (name "GNDOSC0") (class "Default")
      (node (ref "R400") (pin "1") (pinfunction "1_1") (pintype "passive"))
      (node (ref "U400") (pin "V11") (pinfunction "VSS_OSC_V11") (pintype "power_in"))
    )
    (net (code "17") (name "GNDOSC1") (class "Default")
      (node (ref "R401") (pin "2") (pinfunction "2_2") (pintype "passive"))
      (node (ref "U400") (pin "A5") (pinfunction "VSS_RTC_A5") (pintype "power_in"))
    )
    (net (code "18") (name "VDD_ADC") (class "Default")
      (node (ref "C409") (pin "2") (pinfunction "2_2") (pintype "passive"))
      (node (ref "FB402") (pin "2") (pinfunction "2_2") (pintype "passive"))
      (node (ref "U400") (pin "D8") (pinfunction "VDDA_ADC_D8") (pintype "power_in"))
    )
    (net (code "19") (name "VDD_PLL") (class "Default")
      (node (ref "C405") (pin "2") (pinfunction "2_2") (pintype "passive"))
      (node (ref "C406") (pin "2") (pinfunction "2_2") (pintype "passive"))
      (node (ref "C407") (pin "2") (pinfunction "2_2") (pintype "passive"))
      (node (ref "C410") (pin "2") (pinfunction "2_2") (pintype "passive"))
      (node (ref "FB401") (pin "2") (pinfunction "2_2") (pintype "passive"))
      (node (ref "U400") (pin "E7") (pinfunction "VDDS_PLL_DDR_E7") (pintype "power_in"))
      (node (ref "U400") (pin "H15") (pinfunction "VDDS_PLL_MPU_H15") (pintype "power_in"))
      (node (ref "U400") (pin "R10") (pinfunction "VDDS_PLL_CORE_LCD_R10") (pintype "power_in"))
      (node (ref "U400") (pin "R11") (pinfunction "VDDS_OSC_R11") (pintype "power_in"))
    )
    (net (code "20") (name "unconnected-(R402-Pad2)") (class "Default")
      (node (ref "R402") (pin "2") (pinfunction "2_2") (pintype "passive+no_connect"))
    )
  )
)
